# ToolDoorController_edge.net
KiCad netlist of a schematic drawn in Altium Designer
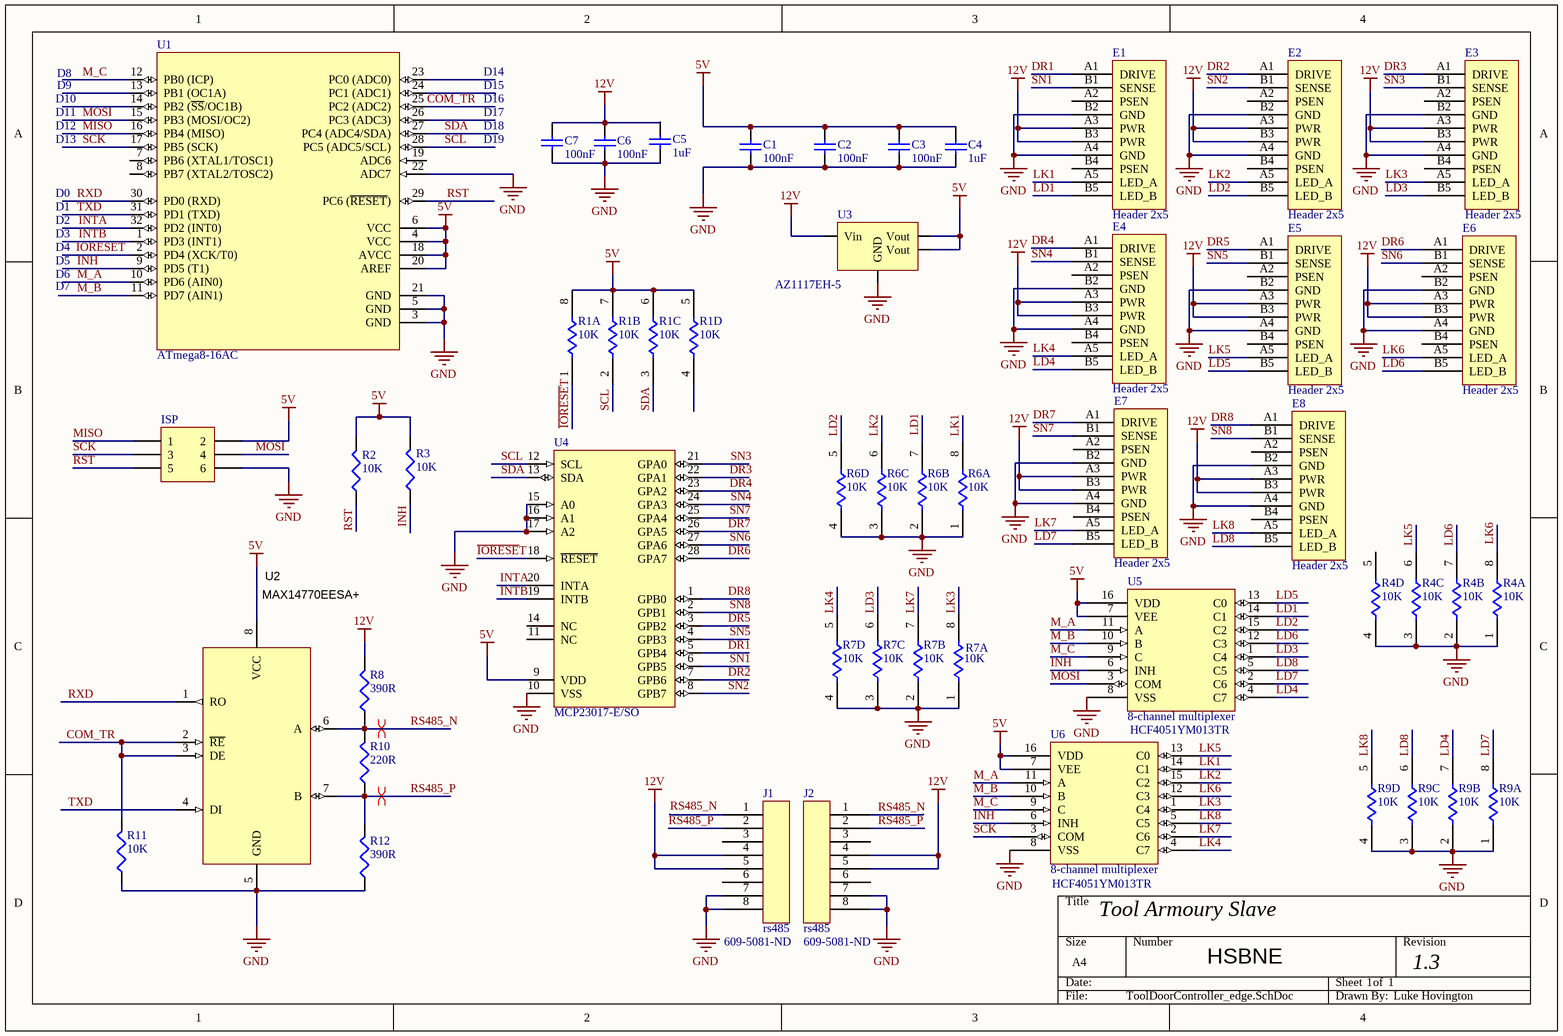
[diagram p0: ToolDoorController_edge.SchDoc]

(export (version "E")
  (design (tool "Eeschema 10.0.6"))
  (components
    (comp (ref "C1")
      (value "100nF")
      (footprint "C1206")
      (description "Capacitor (Semiconductor SIM Model)")
      (fields (field (name "PUBLISHER") "Altium Limited"))
      (libsource (lib "ToolDoorController") (part "Cap 100nF"))
    )
    (comp (ref "C2")
      (value "100nF")
      (footprint "C1206")
      (description "Capacitor (Semiconductor SIM Model)")
      (fields (field (name "PUBLISHER") "Altium Limited"))
      (libsource (lib "ToolDoorController") (part "Cap 100nF"))
    )
    (comp (ref "C3")
      (value "100nF")
      (footprint "C1206")
      (description "Capacitor (Semiconductor SIM Model)")
      (fields (field (name "PUBLISHER") "Altium Limited"))
      (libsource (lib "ToolDoorController") (part "Cap 100nF"))
    )
    (comp (ref "C4")
      (value "1uF")
      (footprint "C1206")
      (description "Capacitor (Semiconductor SIM Model)")
      (fields (field (name "PUBLISHER") "Altium Limited"))
      (libsource (lib "ToolDoorController") (part "Cap 1uF"))
    )
    (comp (ref "C5")
      (value "1uF")
      (footprint "C1206")
      (description "Capacitor (Semiconductor SIM Model)")
      (fields (field (name "PUBLISHER") "Altium Limited"))
      (libsource (lib "ToolDoorController") (part "Cap 1uF"))
    )
    (comp (ref "C6")
      (value "100nF")
      (footprint "C1206")
      (description "Capacitor (Semiconductor SIM Model)")
      (fields (field (name "PUBLISHER") "Altium Limited"))
      (libsource (lib "ToolDoorController") (part "Cap 100nF"))
    )
    (comp (ref "C7")
      (value "100nF")
      (footprint "C1206")
      (description "Capacitor (Semiconductor SIM Model)")
      (fields (field (name "PUBLISHER") "Altium Limited"))
      (libsource (lib "ToolDoorController") (part "Cap 100nF"))
    )
    (comp (ref "E1")
      (value "Header 2x5")
      (footprint "CARDEDGE CWR-170-10")
      (description "Header")
      (libsource (lib "ToolDoorController") (part "Header 2x5"))
    )
    (comp (ref "E2")
      (value "Header 2x5")
      (footprint "CARDEDGE CWR-170-10")
      (description "Header")
      (libsource (lib "ToolDoorController") (part "Header 2x5"))
    )
    (comp (ref "E3")
      (value "Header 2x5")
      (footprint "CARDEDGE CWR-170-10")
      (description "Header")
      (libsource (lib "ToolDoorController") (part "Header 2x5"))
    )
    (comp (ref "E4")
      (value "Header 2x5")
      (footprint "CARDEDGE CWR-170-10")
      (description "Header")
      (libsource (lib "ToolDoorController") (part "Header 2x5"))
    )
    (comp (ref "E5")
      (value "Header 2x5")
      (footprint "CARDEDGE CWR-170-10")
      (description "Header")
      (libsource (lib "ToolDoorController") (part "Header 2x5"))
    )
    (comp (ref "E6")
      (value "Header 2x5")
      (footprint "CARDEDGE CWR-170-10")
      (description "Header")
      (libsource (lib "ToolDoorController") (part "Header 2x5"))
    )
    (comp (ref "E7")
      (value "Header 2x5")
      (footprint "CARDEDGE CWR-170-10")
      (description "Header")
      (libsource (lib "ToolDoorController") (part "Header 2x5"))
    )
    (comp (ref "E8")
      (value "Header 2x5")
      (footprint "CARDEDGE CWR-170-10")
      (description "Header")
      (libsource (lib "ToolDoorController") (part "Header 2x5"))
    )
    (comp (ref "ISP")
      (value "ISP")
      (footprint "HDR2X3")
      (description "Header, 3-Pin, Dual row")
      (fields (field (name "PUBLISHER") "Altium Limited"))
      (libsource (lib "ToolDoorController") (part "Header 3X2"))
    )
    (comp (ref "J1")
      (value "rs485")
      (footprint "RJ45")
      (description "rj45")
      (fields (field (name "SUPPLIER PART NUMBER 1") "609-5081-ND"))
      (libsource (lib "") (part "rj45_1"))
    )
    (comp (ref "J2")
      (value "rs485")
      (footprint "RJ45")
      (description "rj45")
      (fields (field (name "SUPPLIER PART NUMBER 1") "609-5081-ND"))
      (libsource (lib "ToolDoorController") (part "rj45"))
    )
    (comp (ref "R1")
      (value "10K")
      (footprint "SO8_S")
      (description "Isolated Resistor Network - Parts")
      (fields (field (name "PUBLISHER") "Altium Limited"))
      (libsource (lib "ToolDoorController") (part "Resistor Pack"))
    )
    (comp (ref "R2")
      (value "10K")
      (footprint "C1206")
      (description "Resistor")
      (fields (field (name "PUBLISHER") "Altium Limited"))
      (libsource (lib "ToolDoorController") (part "Resistor-10K"))
    )
    (comp (ref "R3")
      (value "10K")
      (footprint "C1206")
      (description "Resistor")
      (fields (field (name "PUBLISHER") "Altium Limited"))
      (libsource (lib "ToolDoorController") (part "Resistor-10K"))
    )
    (comp (ref "R4")
      (value "10K")
      (footprint "SO8_S")
      (description "Isolated Resistor Network - Parts")
      (fields (field (name "PUBLISHER") "Altium Limited"))
      (libsource (lib "ToolDoorController") (part "Resistor Pack"))
    )
    (comp (ref "R6")
      (value "10K")
      (footprint "SO8_S")
      (description "Isolated Resistor Network - Parts")
      (fields (field (name "PUBLISHER") "Altium Limited"))
      (libsource (lib "ToolDoorController") (part "Resistor Pack"))
    )
    (comp (ref "R7")
      (value "10K")
      (footprint "SO8_S")
      (description "Isolated Resistor Network - Parts")
      (fields (field (name "PUBLISHER") "Altium Limited"))
      (libsource (lib "ToolDoorController") (part "Resistor Pack"))
    )
    (comp (ref "R8")
      (value "390R")
      (footprint "C1206")
      (description "Resistor")
      (fields (field (name "PUBLISHER") "Altium Limited"))
      (libsource (lib "ToolDoorController") (part "Resistor-390R"))
    )
    (comp (ref "R9")
      (value "10K")
      (footprint "SO8_S")
      (description "Isolated Resistor Network - Parts")
      (fields (field (name "PUBLISHER") "Altium Limited"))
      (libsource (lib "ToolDoorController") (part "Resistor Pack"))
    )
    (comp (ref "R10")
      (value "220R")
      (footprint "C1206")
      (description "Resistor")
      (fields (field (name "PUBLISHER") "Altium Limited"))
      (libsource (lib "ToolDoorController") (part "Resistor-220R"))
    )
    (comp (ref "R11")
      (value "10K")
      (footprint "C1206")
      (description "Resistor")
      (fields (field (name "PUBLISHER") "Altium Limited"))
      (libsource (lib "ToolDoorController") (part "Resistor-10K"))
    )
    (comp (ref "R12")
      (value "390R")
      (footprint "C1206")
      (description "Resistor")
      (fields (field (name "PUBLISHER") "Altium Limited"))
      (libsource (lib "ToolDoorController") (part "Resistor-390R"))
    )
    (comp (ref "U1")
      (value "ATmega8-16AC")
      (footprint "32A_N")
      (description "8-Bit AVR Microcontroller with 8K Bytes of In-System Programmable Flash Memory")
      (fields (field (name "PUBLISHER") "Altium Limited"))
      (libsource (lib "ToolDoorController") (part "ATmega8-16AC"))
    )
    (comp (ref "U2")
      (value "MAX14770EESA+")
      (footprint "8S1_L")
      (description "TXRX PROFIBUS RS-485 8-SOIC")
      (libsource (lib "ToolDoorController") (part "MAX14770EESA+"))
    )
    (comp (ref "U3")
      (value "AZ1117EH-5")
      (footprint "SOT-223")
      (description "Reg 1A 5V OUT SIP VERT")
      (libsource (lib "ToolDoorController") (part "AZ1117EH"))
    )
    (comp (ref "U4")
      (value "MCP23017-E/SO")
      (footprint "SOIC-SO28_N")
      (description "16-Bit I/O Expander with Serial Interface, 28-Pin SOIC, Extended Temperature")
      (libsource (lib "Altium Content Vault") (part "PR-BUSIC-MCP23017-28"))
    )
    (comp (ref "U5")
      (value "8-channel multiplexer")
      (footprint "16S1_M")
      (description "8-channel analog multiplexer/demultiplexer")
      (fields (field (name "MANUFACTURER PART NUMBER") "HCF4051YM013TR"))
      (libsource (lib "ToolDoorController") (part "8-channel multiplexer"))
    )
    (comp (ref "U6")
      (value "8-channel multiplexer")
      (footprint "16S1_M")
      (description "8-channel analog multiplexer/demultiplexer")
      (fields (field (name "MANUFACTURER PART NUMBER") "HCF4051YM013TR"))
      (libsource (lib "ToolDoorController") (part "8-channel multiplexer"))
    )
  )
  (nets
    (net (code "1") (name "/COM_TR") (class "Default")
      (node (ref "R11") (pin "2") (pinfunction "2_2") (pintype "passive"))
      (node (ref "U1") (pin "25") (pinfunction "PC2_(ADC2)_25") (pintype "bidirectional"))
      (node (ref "U2") (pin "2") (pinfunction "~{RE}_2") (pintype "input"))
      (node (ref "U2") (pin "3") (pinfunction "DE_3") (pintype "input"))
    )
    (net (code "2") (name "/DR1") (class "Default")
      (node (ref "E1") (pin "A1") (pinfunction "DRIVE_A1") (pintype "power_in"))
      (node (ref "U4") (pin "5") (pinfunction "GPB4_5") (pintype "bidirectional"))
    )
    (net (code "3") (name "/DR2") (class "Default")
      (node (ref "E2") (pin "A1") (pinfunction "DRIVE_A1") (pintype "power_in"))
      (node (ref "U4") (pin "7") (pinfunction "GPB6_7") (pintype "bidirectional"))
    )
    (net (code "4") (name "/DR3") (class "Default")
      (node (ref "E3") (pin "A1") (pinfunction "DRIVE_A1") (pintype "power_in"))
      (node (ref "U4") (pin "22") (pinfunction "GPA1_22") (pintype "bidirectional"))
    )
    (net (code "5") (name "/DR4") (class "Default")
      (node (ref "E4") (pin "A1") (pinfunction "DRIVE_A1") (pintype "power_in"))
      (node (ref "U4") (pin "23") (pinfunction "GPA2_23") (pintype "bidirectional"))
    )
    (net (code "6") (name "/DR5") (class "Default")
      (node (ref "E5") (pin "A1") (pinfunction "DRIVE_A1") (pintype "power_in"))
      (node (ref "U4") (pin "3") (pinfunction "GPB2_3") (pintype "bidirectional"))
    )
    (net (code "7") (name "/DR6") (class "Default")
      (node (ref "E6") (pin "A1") (pinfunction "DRIVE_A1") (pintype "power_in"))
      (node (ref "U4") (pin "28") (pinfunction "GPA7_28") (pintype "bidirectional"))
    )
    (net (code "8") (name "/DR7") (class "Default")
      (node (ref "E7") (pin "A1") (pinfunction "DRIVE_A1") (pintype "power_in"))
      (node (ref "U4") (pin "26") (pinfunction "GPA5_26") (pintype "bidirectional"))
    )
    (net (code "9") (name "/DR8") (class "Default")
      (node (ref "E8") (pin "A1") (pinfunction "DRIVE_A1") (pintype "power_in"))
      (node (ref "U4") (pin "1") (pinfunction "GPB0_1") (pintype "bidirectional"))
    )
    (net (code "10") (name "/INH") (class "Default")
      (node (ref "R3") (pin "1") (pinfunction "1_1") (pintype "passive"))
      (node (ref "U1") (pin "9") (pinfunction "PD5_(T1)_9") (pintype "bidirectional"))
      (node (ref "U5") (pin "6") (pinfunction "INH_6") (pintype "input"))
      (node (ref "U6") (pin "6") (pinfunction "INH_6") (pintype "input"))
    )
    (net (code "11") (name "/INTA") (class "Default")
      (node (ref "U1") (pin "32") (pinfunction "PD2_(INT0)_32") (pintype "bidirectional"))
      (node (ref "U4") (pin "20") (pinfunction "INTA_20") (pintype "open_collector"))
    )
    (net (code "12") (name "/INTB") (class "Default")
      (node (ref "U1") (pin "1") (pinfunction "PD3_(INT1)_1") (pintype "bidirectional"))
      (node (ref "U4") (pin "19") (pinfunction "INTB_19") (pintype "open_collector"))
    )
    (net (code "13") (name "/LD1") (class "Default")
      (node (ref "E1") (pin "B5") (pinfunction "LED_B_B5") (pintype "power_in"))
      (node (ref "R6") (pin "7") (pinfunction "7_7") (pintype "passive"))
      (node (ref "U5") (pin "14") (pinfunction "C1_14") (pintype "bidirectional"))
    )
    (net (code "14") (name "/LD2") (class "Default")
      (node (ref "E2") (pin "B5") (pinfunction "LED_B_B5") (pintype "power_in"))
      (node (ref "R6") (pin "5") (pinfunction "5_5") (pintype "passive"))
      (node (ref "U5") (pin "15") (pinfunction "C2_15") (pintype "bidirectional"))
    )
    (net (code "15") (name "/LD3") (class "Default")
      (node (ref "E3") (pin "B5") (pinfunction "LED_B_B5") (pintype "power_in"))
      (node (ref "R7") (pin "6") (pinfunction "6_6") (pintype "passive"))
      (node (ref "U5") (pin "1") (pinfunction "C4_1") (pintype "bidirectional"))
    )
    (net (code "16") (name "/LD4") (class "Default")
      (node (ref "E4") (pin "B5") (pinfunction "LED_B_B5") (pintype "power_in"))
      (node (ref "R9") (pin "7") (pinfunction "7_7") (pintype "passive"))
      (node (ref "U5") (pin "4") (pinfunction "C7_4") (pintype "bidirectional"))
    )
    (net (code "17") (name "/LD5") (class "Default")
      (node (ref "E5") (pin "B5") (pinfunction "LED_B_B5") (pintype "power_in"))
      (node (ref "U5") (pin "13") (pinfunction "C0_13") (pintype "bidirectional"))
    )
    (net (code "18") (name "/LD6") (class "Default")
      (node (ref "E6") (pin "B5") (pinfunction "LED_B_B5") (pintype "power_in"))
      (node (ref "R4") (pin "7") (pinfunction "7_7") (pintype "passive"))
      (node (ref "U5") (pin "12") (pinfunction "C3_12") (pintype "bidirectional"))
    )
    (net (code "19") (name "/LD7") (class "Default")
      (node (ref "E7") (pin "B5") (pinfunction "LED_B_B5") (pintype "power_in"))
      (node (ref "R9") (pin "8") (pinfunction "8_8") (pintype "passive"))
      (node (ref "U5") (pin "2") (pinfunction "C6_2") (pintype "bidirectional"))
    )
    (net (code "20") (name "/LD8") (class "Default")
      (node (ref "E8") (pin "B5") (pinfunction "LED_B_B5") (pintype "power_in"))
      (node (ref "R9") (pin "6") (pinfunction "6_6") (pintype "passive"))
      (node (ref "U5") (pin "5") (pinfunction "C5_5") (pintype "bidirectional"))
    )
    (net (code "21") (name "/LK1") (class "Default")
      (node (ref "E1") (pin "A5") (pinfunction "LED_A_A5") (pintype "power_in"))
      (node (ref "R6") (pin "8") (pinfunction "8_8") (pintype "passive"))
      (node (ref "U6") (pin "14") (pinfunction "C1_14") (pintype "bidirectional"))
    )
    (net (code "22") (name "/LK2") (class "Default")
      (node (ref "E2") (pin "A5") (pinfunction "LED_A_A5") (pintype "power_in"))
      (node (ref "R6") (pin "6") (pinfunction "6_6") (pintype "passive"))
      (node (ref "U6") (pin "15") (pinfunction "C2_15") (pintype "bidirectional"))
    )
    (net (code "23") (name "/LK3") (class "Default")
      (node (ref "E3") (pin "A5") (pinfunction "LED_A_A5") (pintype "power_in"))
      (node (ref "R7") (pin "8") (pinfunction "8_8") (pintype "passive"))
      (node (ref "U6") (pin "1") (pinfunction "C4_1") (pintype "bidirectional"))
    )
    (net (code "24") (name "/LK4") (class "Default")
      (node (ref "E4") (pin "A5") (pinfunction "LED_A_A5") (pintype "power_in"))
      (node (ref "R7") (pin "5") (pinfunction "5_5") (pintype "passive"))
      (node (ref "U6") (pin "4") (pinfunction "C7_4") (pintype "bidirectional"))
    )
    (net (code "25") (name "/LK5") (class "Default")
      (node (ref "E5") (pin "A5") (pinfunction "LED_A_A5") (pintype "power_in"))
      (node (ref "R4") (pin "6") (pinfunction "6_6") (pintype "passive"))
      (node (ref "U6") (pin "13") (pinfunction "C0_13") (pintype "bidirectional"))
    )
    (net (code "26") (name "/LK6") (class "Default")
      (node (ref "E6") (pin "A5") (pinfunction "LED_A_A5") (pintype "power_in"))
      (node (ref "R4") (pin "8") (pinfunction "8_8") (pintype "passive"))
      (node (ref "U6") (pin "12") (pinfunction "C3_12") (pintype "bidirectional"))
    )
    (net (code "27") (name "/LK7") (class "Default")
      (node (ref "E7") (pin "A5") (pinfunction "LED_A_A5") (pintype "power_in"))
      (node (ref "R7") (pin "7") (pinfunction "7_7") (pintype "passive"))
      (node (ref "U6") (pin "2") (pinfunction "C6_2") (pintype "bidirectional"))
    )
    (net (code "28") (name "/LK8") (class "Default")
      (node (ref "E8") (pin "A5") (pinfunction "LED_A_A5") (pintype "power_in"))
      (node (ref "R9") (pin "5") (pinfunction "5_5") (pintype "passive"))
      (node (ref "U6") (pin "5") (pinfunction "C5_5") (pintype "bidirectional"))
    )
    (net (code "29") (name "/MISO") (class "Default")
      (node (ref "ISP") (pin "1") (pinfunction "1_1") (pintype "passive"))
      (node (ref "U1") (pin "16") (pinfunction "PB4_(MISO)_16") (pintype "bidirectional"))
    )
    (net (code "30") (name "/MOSI") (class "Default")
      (node (ref "ISP") (pin "4") (pinfunction "4_4") (pintype "passive"))
      (node (ref "U1") (pin "15") (pinfunction "PB3_(MOSI/OC2)_15") (pintype "bidirectional"))
      (node (ref "U5") (pin "3") (pinfunction "COM_3") (pintype "bidirectional"))
    )
    (net (code "31") (name "/M_A") (class "Default")
      (node (ref "U1") (pin "10") (pinfunction "PD6_(AIN0)_10") (pintype "bidirectional"))
      (node (ref "U5") (pin "11") (pinfunction "A_11") (pintype "input"))
      (node (ref "U6") (pin "11") (pinfunction "A_11") (pintype "input"))
    )
    (net (code "32") (name "/M_B") (class "Default")
      (node (ref "U1") (pin "11") (pinfunction "PD7_(AIN1)_11") (pintype "bidirectional"))
      (node (ref "U5") (pin "10") (pinfunction "B_10") (pintype "input"))
      (node (ref "U6") (pin "10") (pinfunction "B_10") (pintype "input"))
    )
    (net (code "33") (name "/M_C") (class "Default")
      (node (ref "U1") (pin "12") (pinfunction "PB0_(ICP)_12") (pintype "bidirectional"))
      (node (ref "U5") (pin "9") (pinfunction "C_9") (pintype "input"))
      (node (ref "U6") (pin "9") (pinfunction "C_9") (pintype "input"))
    )
    (net (code "34") (name "/RS485_N") (class "Default")
      (node (ref "J1") (pin "1") (pinfunction "1_1") (pintype "power_in"))
      (node (ref "J2") (pin "1") (pinfunction "1_1") (pintype "power_in"))
      (node (ref "R10") (pin "2") (pinfunction "2_2") (pintype "passive"))
      (node (ref "R8") (pin "1") (pinfunction "1_1") (pintype "passive"))
      (node (ref "U2") (pin "6") (pinfunction "A_6") (pintype "bidirectional"))
    )
    (net (code "35") (name "/RS485_P") (class "Default")
      (node (ref "J1") (pin "2") (pinfunction "2_2") (pintype "power_in"))
      (node (ref "J2") (pin "2") (pinfunction "2_2") (pintype "power_in"))
      (node (ref "R10") (pin "1") (pinfunction "1_1") (pintype "passive"))
      (node (ref "R12") (pin "2") (pinfunction "2_2") (pintype "passive"))
      (node (ref "U2") (pin "7") (pinfunction "B_7") (pintype "bidirectional"))
    )
    (net (code "36") (name "/RST") (class "Default")
      (node (ref "ISP") (pin "5") (pinfunction "5_5") (pintype "passive"))
      (node (ref "R2") (pin "1") (pinfunction "1_1") (pintype "passive"))
      (node (ref "U1") (pin "29") (pinfunction "PC6_(~{RESET})_29") (pintype "bidirectional"))
    )
    (net (code "37") (name "/RXD") (class "Default")
      (node (ref "U1") (pin "30") (pinfunction "PD0_(RXD)_30") (pintype "bidirectional"))
      (node (ref "U2") (pin "1") (pinfunction "RO_1") (pintype "output"))
    )
    (net (code "38") (name "/SCK") (class "Default")
      (node (ref "ISP") (pin "3") (pinfunction "3_3") (pintype "passive"))
      (node (ref "U1") (pin "17") (pinfunction "PB5_(SCK)_17") (pintype "bidirectional"))
      (node (ref "U6") (pin "3") (pinfunction "COM_3") (pintype "bidirectional"))
    )
    (net (code "39") (name "/SCL") (class "Default")
      (node (ref "R1") (pin "2") (pinfunction "2_2") (pintype "passive"))
      (node (ref "U1") (pin "28") (pinfunction "PC5_(ADC5/SCL)_28") (pintype "bidirectional"))
      (node (ref "U4") (pin "12") (pinfunction "SCL_12") (pintype "input"))
    )
    (net (code "40") (name "/SDA") (class "Default")
      (node (ref "R1") (pin "3") (pinfunction "3_3") (pintype "passive"))
      (node (ref "U1") (pin "27") (pinfunction "PC4_(ADC4/SDA)_27") (pintype "bidirectional"))
      (node (ref "U4") (pin "13") (pinfunction "SDA_13") (pintype "bidirectional"))
    )
    (net (code "41") (name "/SN1") (class "Default")
      (node (ref "E1") (pin "B1") (pinfunction "SENSE_B1") (pintype "power_in"))
      (node (ref "U4") (pin "6") (pinfunction "GPB5_6") (pintype "bidirectional"))
    )
    (net (code "42") (name "/SN2") (class "Default")
      (node (ref "E2") (pin "B1") (pinfunction "SENSE_B1") (pintype "power_in"))
      (node (ref "U4") (pin "8") (pinfunction "GPB7_8") (pintype "bidirectional"))
    )
    (net (code "43") (name "/SN3") (class "Default")
      (node (ref "E3") (pin "B1") (pinfunction "SENSE_B1") (pintype "power_in"))
      (node (ref "U4") (pin "21") (pinfunction "GPA0_21") (pintype "bidirectional"))
    )
    (net (code "44") (name "/SN4") (class "Default")
      (node (ref "E4") (pin "B1") (pinfunction "SENSE_B1") (pintype "power_in"))
      (node (ref "U4") (pin "24") (pinfunction "GPA3_24") (pintype "bidirectional"))
    )
    (net (code "45") (name "/SN5") (class "Default")
      (node (ref "E5") (pin "B1") (pinfunction "SENSE_B1") (pintype "power_in"))
      (node (ref "U4") (pin "4") (pinfunction "GPB3_4") (pintype "bidirectional"))
    )
    (net (code "46") (name "/SN6") (class "Default")
      (node (ref "E6") (pin "B1") (pinfunction "SENSE_B1") (pintype "power_in"))
      (node (ref "U4") (pin "27") (pinfunction "GPA6_27") (pintype "bidirectional"))
    )
    (net (code "47") (name "/SN7") (class "Default")
      (node (ref "E7") (pin "B1") (pinfunction "SENSE_B1") (pintype "power_in"))
      (node (ref "U4") (pin "25") (pinfunction "GPA4_25") (pintype "bidirectional"))
    )
    (net (code "48") (name "/SN8") (class "Default")
      (node (ref "E8") (pin "B1") (pinfunction "SENSE_B1") (pintype "power_in"))
      (node (ref "U4") (pin "2") (pinfunction "GPB1_2") (pintype "bidirectional"))
    )
    (net (code "49") (name "/TXD") (class "Default")
      (node (ref "U1") (pin "31") (pinfunction "PD1_(TXD)_31") (pintype "bidirectional"))
      (node (ref "U2") (pin "4") (pinfunction "DI_4") (pintype "input"))
    )
    (net (code "50") (name "/~{IORESE}T") (class "Default")
      (node (ref "R1") (pin "1") (pinfunction "1_1") (pintype "passive"))
      (node (ref "U1") (pin "2") (pinfunction "PD4_(XCK/T0)_2") (pintype "bidirectional"))
      (node (ref "U4") (pin "18") (pinfunction "~{RESET}_18") (pintype "input"))
    )
    (net (code "51") (name "5V") (class "Default")
      (node (ref "C1") (pin "2") (pinfunction "2_2") (pintype "passive"))
      (node (ref "C2") (pin "2") (pinfunction "2_2") (pintype "passive"))
      (node (ref "C3") (pin "2") (pinfunction "2_2") (pintype "passive"))
      (node (ref "C4") (pin "2") (pinfunction "2_2") (pintype "passive"))
      (node (ref "ISP") (pin "2") (pinfunction "2_2") (pintype "passive"))
      (node (ref "R1") (pin "5") (pinfunction "5_5") (pintype "passive"))
      (node (ref "R1") (pin "6") (pinfunction "6_6") (pintype "passive"))
      (node (ref "R1") (pin "7") (pinfunction "7_7") (pintype "passive"))
      (node (ref "R1") (pin "8") (pinfunction "8_8") (pintype "passive"))
      (node (ref "R2") (pin "2") (pinfunction "2_2") (pintype "passive"))
      (node (ref "R3") (pin "2") (pinfunction "2_2") (pintype "passive"))
      (node (ref "U1") (pin "18") (pinfunction "AVCC_18") (pintype "power_in"))
      (node (ref "U1") (pin "20") (pinfunction "AREF_20") (pintype "passive"))
      (node (ref "U1") (pin "4") (pinfunction "VCC_4") (pintype "power_in"))
      (node (ref "U1") (pin "6") (pinfunction "VCC_6") (pintype "power_in"))
      (node (ref "U2") (pin "8") (pinfunction "VCC_8") (pintype "power_in"))
      (node (ref "U3") (pin "2") (pinfunction "Vout_2") (pintype "power_in"))
      (node (ref "U3") (pin "4") (pinfunction "Vout_4") (pintype "power_in"))
      (node (ref "U4") (pin "9") (pinfunction "VDD_9") (pintype "power_in"))
      (node (ref "U5") (pin "16") (pinfunction "VDD_16") (pintype "power_in"))
      (node (ref "U5") (pin "7") (pinfunction "VEE_7") (pintype "power_in"))
      (node (ref "U6") (pin "16") (pinfunction "VDD_16") (pintype "power_in"))
      (node (ref "U6") (pin "7") (pinfunction "VEE_7") (pintype "power_in"))
    )
    (net (code "52") (name "12V") (class "Default")
      (node (ref "C5") (pin "2") (pinfunction "2_2") (pintype "passive"))
      (node (ref "C6") (pin "2") (pinfunction "2_2") (pintype "passive"))
      (node (ref "C7") (pin "2") (pinfunction "2_2") (pintype "passive"))
      (node (ref "E1") (pin "A3") (pinfunction "PWR_A3") (pintype "power_in"))
      (node (ref "E1") (pin "B3") (pinfunction "PWR_B3") (pintype "power_in"))
      (node (ref "E2") (pin "A3") (pinfunction "PWR_A3") (pintype "power_in"))
      (node (ref "E2") (pin "B3") (pinfunction "PWR_B3") (pintype "power_in"))
      (node (ref "E3") (pin "A3") (pinfunction "PWR_A3") (pintype "power_in"))
      (node (ref "E3") (pin "B3") (pinfunction "PWR_B3") (pintype "power_in"))
      (node (ref "E4") (pin "A3") (pinfunction "PWR_A3") (pintype "power_in"))
      (node (ref "E4") (pin "B3") (pinfunction "PWR_B3") (pintype "power_in"))
      (node (ref "E5") (pin "A3") (pinfunction "PWR_A3") (pintype "power_in"))
      (node (ref "E5") (pin "B3") (pinfunction "PWR_B3") (pintype "power_in"))
      (node (ref "E6") (pin "A3") (pinfunction "PWR_A3") (pintype "power_in"))
      (node (ref "E6") (pin "B3") (pinfunction "PWR_B3") (pintype "power_in"))
      (node (ref "E7") (pin "A3") (pinfunction "PWR_A3") (pintype "power_in"))
      (node (ref "E7") (pin "B3") (pinfunction "PWR_B3") (pintype "power_in"))
      (node (ref "E8") (pin "A3") (pinfunction "PWR_A3") (pintype "power_in"))
      (node (ref "E8") (pin "B3") (pinfunction "PWR_B3") (pintype "power_in"))
      (node (ref "J1") (pin "4") (pinfunction "4_4") (pintype "power_in"))
      (node (ref "J1") (pin "5") (pinfunction "5_5") (pintype "power_in"))
      (node (ref "J2") (pin "4") (pinfunction "4_4") (pintype "power_in"))
      (node (ref "J2") (pin "5") (pinfunction "5_5") (pintype "power_in"))
      (node (ref "R8") (pin "2") (pinfunction "2_2") (pintype "passive"))
      (node (ref "U3") (pin "3") (pinfunction "Vin_3") (pintype "power_in"))
    )
    (net (code "53") (name "GND") (class "Default")
      (node (ref "C1") (pin "1") (pinfunction "1_1") (pintype "passive"))
      (node (ref "C2") (pin "1") (pinfunction "1_1") (pintype "passive"))
      (node (ref "C3") (pin "1") (pinfunction "1_1") (pintype "passive"))
      (node (ref "C4") (pin "1") (pinfunction "1_1") (pintype "passive"))
      (node (ref "C5") (pin "1") (pinfunction "1_1") (pintype "passive"))
      (node (ref "C6") (pin "1") (pinfunction "1_1") (pintype "passive"))
      (node (ref "C7") (pin "1") (pinfunction "1_1") (pintype "passive"))
      (node (ref "E1") (pin "A4") (pinfunction "GND_A4") (pintype "power_in"))
      (node (ref "E1") (pin "B2") (pinfunction "GND_B2") (pintype "power_in"))
      (node (ref "E2") (pin "A4") (pinfunction "GND_A4") (pintype "power_in"))
      (node (ref "E2") (pin "B2") (pinfunction "GND_B2") (pintype "power_in"))
      (node (ref "E3") (pin "A4") (pinfunction "GND_A4") (pintype "power_in"))
      (node (ref "E3") (pin "B2") (pinfunction "GND_B2") (pintype "power_in"))
      (node (ref "E4") (pin "A4") (pinfunction "GND_A4") (pintype "power_in"))
      (node (ref "E4") (pin "B2") (pinfunction "GND_B2") (pintype "power_in"))
      (node (ref "E5") (pin "A4") (pinfunction "GND_A4") (pintype "power_in"))
      (node (ref "E5") (pin "B2") (pinfunction "GND_B2") (pintype "power_in"))
      (node (ref "E6") (pin "A4") (pinfunction "GND_A4") (pintype "power_in"))
      (node (ref "E6") (pin "B2") (pinfunction "GND_B2") (pintype "power_in"))
      (node (ref "E7") (pin "A4") (pinfunction "GND_A4") (pintype "power_in"))
      (node (ref "E7") (pin "B2") (pinfunction "GND_B2") (pintype "power_in"))
      (node (ref "E8") (pin "A4") (pinfunction "GND_A4") (pintype "power_in"))
      (node (ref "E8") (pin "B2") (pinfunction "GND_B2") (pintype "power_in"))
      (node (ref "ISP") (pin "6") (pinfunction "6_6") (pintype "passive"))
      (node (ref "J1") (pin "7") (pinfunction "7_7") (pintype "power_in"))
      (node (ref "J1") (pin "8") (pinfunction "8_8") (pintype "power_in"))
      (node (ref "J2") (pin "7") (pinfunction "7_7") (pintype "power_in"))
      (node (ref "J2") (pin "8") (pinfunction "8_8") (pintype "power_in"))
      (node (ref "R11") (pin "1") (pinfunction "1_1") (pintype "passive"))
      (node (ref "R12") (pin "1") (pinfunction "1_1") (pintype "passive"))
      (node (ref "R4") (pin "1") (pinfunction "1_1") (pintype "passive"))
      (node (ref "R4") (pin "2") (pinfunction "2_2") (pintype "passive"))
      (node (ref "R4") (pin "3") (pinfunction "3_3") (pintype "passive"))
      (node (ref "R4") (pin "4") (pinfunction "4_4") (pintype "passive"))
      (node (ref "R6") (pin "1") (pinfunction "1_1") (pintype "passive"))
      (node (ref "R6") (pin "2") (pinfunction "2_2") (pintype "passive"))
      (node (ref "R6") (pin "3") (pinfunction "3_3") (pintype "passive"))
      (node (ref "R6") (pin "4") (pinfunction "4_4") (pintype "passive"))
      (node (ref "R7") (pin "1") (pinfunction "1_1") (pintype "passive"))
      (node (ref "R7") (pin "2") (pinfunction "2_2") (pintype "passive"))
      (node (ref "R7") (pin "3") (pinfunction "3_3") (pintype "passive"))
      (node (ref "R7") (pin "4") (pinfunction "4_4") (pintype "passive"))
      (node (ref "R9") (pin "1") (pinfunction "1_1") (pintype "passive"))
      (node (ref "R9") (pin "2") (pinfunction "2_2") (pintype "passive"))
      (node (ref "R9") (pin "3") (pinfunction "3_3") (pintype "passive"))
      (node (ref "R9") (pin "4") (pinfunction "4_4") (pintype "passive"))
      (node (ref "U1") (pin "21") (pinfunction "GND_21") (pintype "power_in"))
      (node (ref "U1") (pin "22") (pinfunction "ADC7_22") (pintype "input"))
      (node (ref "U1") (pin "3") (pinfunction "GND_3") (pintype "power_in"))
      (node (ref "U1") (pin "5") (pinfunction "GND_5") (pintype "power_in"))
      (node (ref "U2") (pin "5") (pinfunction "GND_5") (pintype "power_in"))
      (node (ref "U3") (pin "1") (pinfunction "GND_1") (pintype "power_in"))
      (node (ref "U4") (pin "10") (pinfunction "VSS_10") (pintype "power_in"))
      (node (ref "U4") (pin "15") (pinfunction "A0_15") (pintype "input"))
      (node (ref "U4") (pin "16") (pinfunction "A1_16") (pintype "input"))
      (node (ref "U4") (pin "17") (pinfunction "A2_17") (pintype "input"))
      (node (ref "U5") (pin "8") (pinfunction "VSS_8") (pintype "power_in"))
      (node (ref "U6") (pin "8") (pinfunction "VSS_8") (pintype "power_in"))
    )
    (net (code "54") (name "unconnected-(E1-PSEN-PadA2)") (class "Default")
      (node (ref "E1") (pin "A2") (pinfunction "PSEN_A2") (pintype "power_in"))
    )
    (net (code "55") (name "unconnected-(E1-PSEN-PadB4)") (class "Default")
      (node (ref "E1") (pin "B4") (pinfunction "PSEN_B4") (pintype "power_in"))
    )
    (net (code "56") (name "unconnected-(E2-PSEN-PadA2)") (class "Default")
      (node (ref "E2") (pin "A2") (pinfunction "PSEN_A2") (pintype "power_in"))
    )
    (net (code "57") (name "unconnected-(E2-PSEN-PadB4)") (class "Default")
      (node (ref "E2") (pin "B4") (pinfunction "PSEN_B4") (pintype "power_in"))
    )
    (net (code "58") (name "unconnected-(E3-PSEN-PadA2)") (class "Default")
      (node (ref "E3") (pin "A2") (pinfunction "PSEN_A2") (pintype "power_in"))
    )
    (net (code "59") (name "unconnected-(E3-PSEN-PadB4)") (class "Default")
      (node (ref "E3") (pin "B4") (pinfunction "PSEN_B4") (pintype "power_in"))
    )
    (net (code "60") (name "unconnected-(E4-PSEN-PadA2)") (class "Default")
      (node (ref "E4") (pin "A2") (pinfunction "PSEN_A2") (pintype "power_in"))
    )
    (net (code "61") (name "unconnected-(E4-PSEN-PadB4)") (class "Default")
      (node (ref "E4") (pin "B4") (pinfunction "PSEN_B4") (pintype "power_in"))
    )
    (net (code "62") (name "unconnected-(E5-PSEN-PadA2)") (class "Default")
      (node (ref "E5") (pin "A2") (pinfunction "PSEN_A2") (pintype "power_in"))
    )
    (net (code "63") (name "unconnected-(E5-PSEN-PadB4)") (class "Default")
      (node (ref "E5") (pin "B4") (pinfunction "PSEN_B4") (pintype "power_in"))
    )
    (net (code "64") (name "unconnected-(E6-PSEN-PadA2)") (class "Default")
      (node (ref "E6") (pin "A2") (pinfunction "PSEN_A2") (pintype "power_in"))
    )
    (net (code "65") (name "unconnected-(E6-PSEN-PadB4)") (class "Default")
      (node (ref "E6") (pin "B4") (pinfunction "PSEN_B4") (pintype "power_in"))
    )
    (net (code "66") (name "unconnected-(E7-PSEN-PadA2)") (class "Default")
      (node (ref "E7") (pin "A2") (pinfunction "PSEN_A2") (pintype "power_in"))
    )
    (net (code "67") (name "unconnected-(E7-PSEN-PadB4)") (class "Default")
      (node (ref "E7") (pin "B4") (pinfunction "PSEN_B4") (pintype "power_in"))
    )
    (net (code "68") (name "unconnected-(E8-PSEN-PadA2)") (class "Default")
      (node (ref "E8") (pin "A2") (pinfunction "PSEN_A2") (pintype "power_in"))
    )
    (net (code "69") (name "unconnected-(E8-PSEN-PadB4)") (class "Default")
      (node (ref "E8") (pin "B4") (pinfunction "PSEN_B4") (pintype "power_in"))
    )
    (net (code "70") (name "unconnected-(J1-Pad3)") (class "Default")
      (node (ref "J1") (pin "3") (pinfunction "3_3") (pintype "power_in"))
    )
    (net (code "71") (name "unconnected-(J1-Pad6)") (class "Default")
      (node (ref "J1") (pin "6") (pinfunction "6_6") (pintype "power_in"))
    )
    (net (code "72") (name "unconnected-(J2-Pad3)") (class "Default")
      (node (ref "J2") (pin "3") (pinfunction "3_3") (pintype "power_in"))
    )
    (net (code "73") (name "unconnected-(J2-Pad6)") (class "Default")
      (node (ref "J2") (pin "6") (pinfunction "6_6") (pintype "power_in"))
    )
    (net (code "74") (name "unconnected-(R1-Pad4)") (class "Default")
      (node (ref "R1") (pin "4") (pinfunction "4_4") (pintype "passive"))
    )
    (net (code "75") (name "unconnected-(R4-Pad5)") (class "Default")
      (node (ref "R4") (pin "5") (pinfunction "5_5") (pintype "passive"))
    )
    (net (code "76") (name "unconnected-(U1-ADC6-Pad19)") (class "Default")
      (node (ref "U1") (pin "19") (pinfunction "ADC6_19") (pintype "input"))
    )
    (net (code "77") (name "unconnected-(U1-PB1_(OC1A)-Pad13)") (class "Default")
      (node (ref "U1") (pin "13") (pinfunction "PB1_(OC1A)_13") (pintype "bidirectional"))
    )
    (net (code "78") (name "unconnected-(U1-PB2_(~{SS}{slash}OC1B)-Pad14)") (class "Default")
      (node (ref "U1") (pin "14") (pinfunction "PB2_(~{SS}/OC1B)_14") (pintype "bidirectional"))
    )
    (net (code "79") (name "unconnected-(U1-PB6_(XTAL1{slash}TOSC1)-Pad7)") (class "Default")
      (node (ref "U1") (pin "7") (pinfunction "PB6_(XTAL1/TOSC1)_7") (pintype "bidirectional"))
    )
    (net (code "80") (name "unconnected-(U1-PB7_(XTAL2{slash}TOSC2)-Pad8)") (class "Default")
      (node (ref "U1") (pin "8") (pinfunction "PB7_(XTAL2/TOSC2)_8") (pintype "bidirectional"))
    )
    (net (code "81") (name "unconnected-(U1-PC0_(ADC0)-Pad23)") (class "Default")
      (node (ref "U1") (pin "23") (pinfunction "PC0_(ADC0)_23") (pintype "bidirectional"))
    )
    (net (code "82") (name "unconnected-(U1-PC1_(ADC1)-Pad24)") (class "Default")
      (node (ref "U1") (pin "24") (pinfunction "PC1_(ADC1)_24") (pintype "bidirectional"))
    )
    (net (code "83") (name "unconnected-(U1-PC3_(ADC3)-Pad26)") (class "Default")
      (node (ref "U1") (pin "26") (pinfunction "PC3_(ADC3)_26") (pintype "bidirectional"))
    )
    (net (code "84") (name "unconnected-(U4-NC-Pad11)") (class "Default")
      (node (ref "U4") (pin "11") (pinfunction "NC_11") (pintype "passive"))
    )
    (net (code "85") (name "unconnected-(U4-NC-Pad14)") (class "Default")
      (node (ref "U4") (pin "14") (pinfunction "NC_14") (pintype "passive"))
    )
  )
)
